# SCH_orion-rf_2026-05-15.net
KiCad netlist of a schematic drawn in EasyEDA
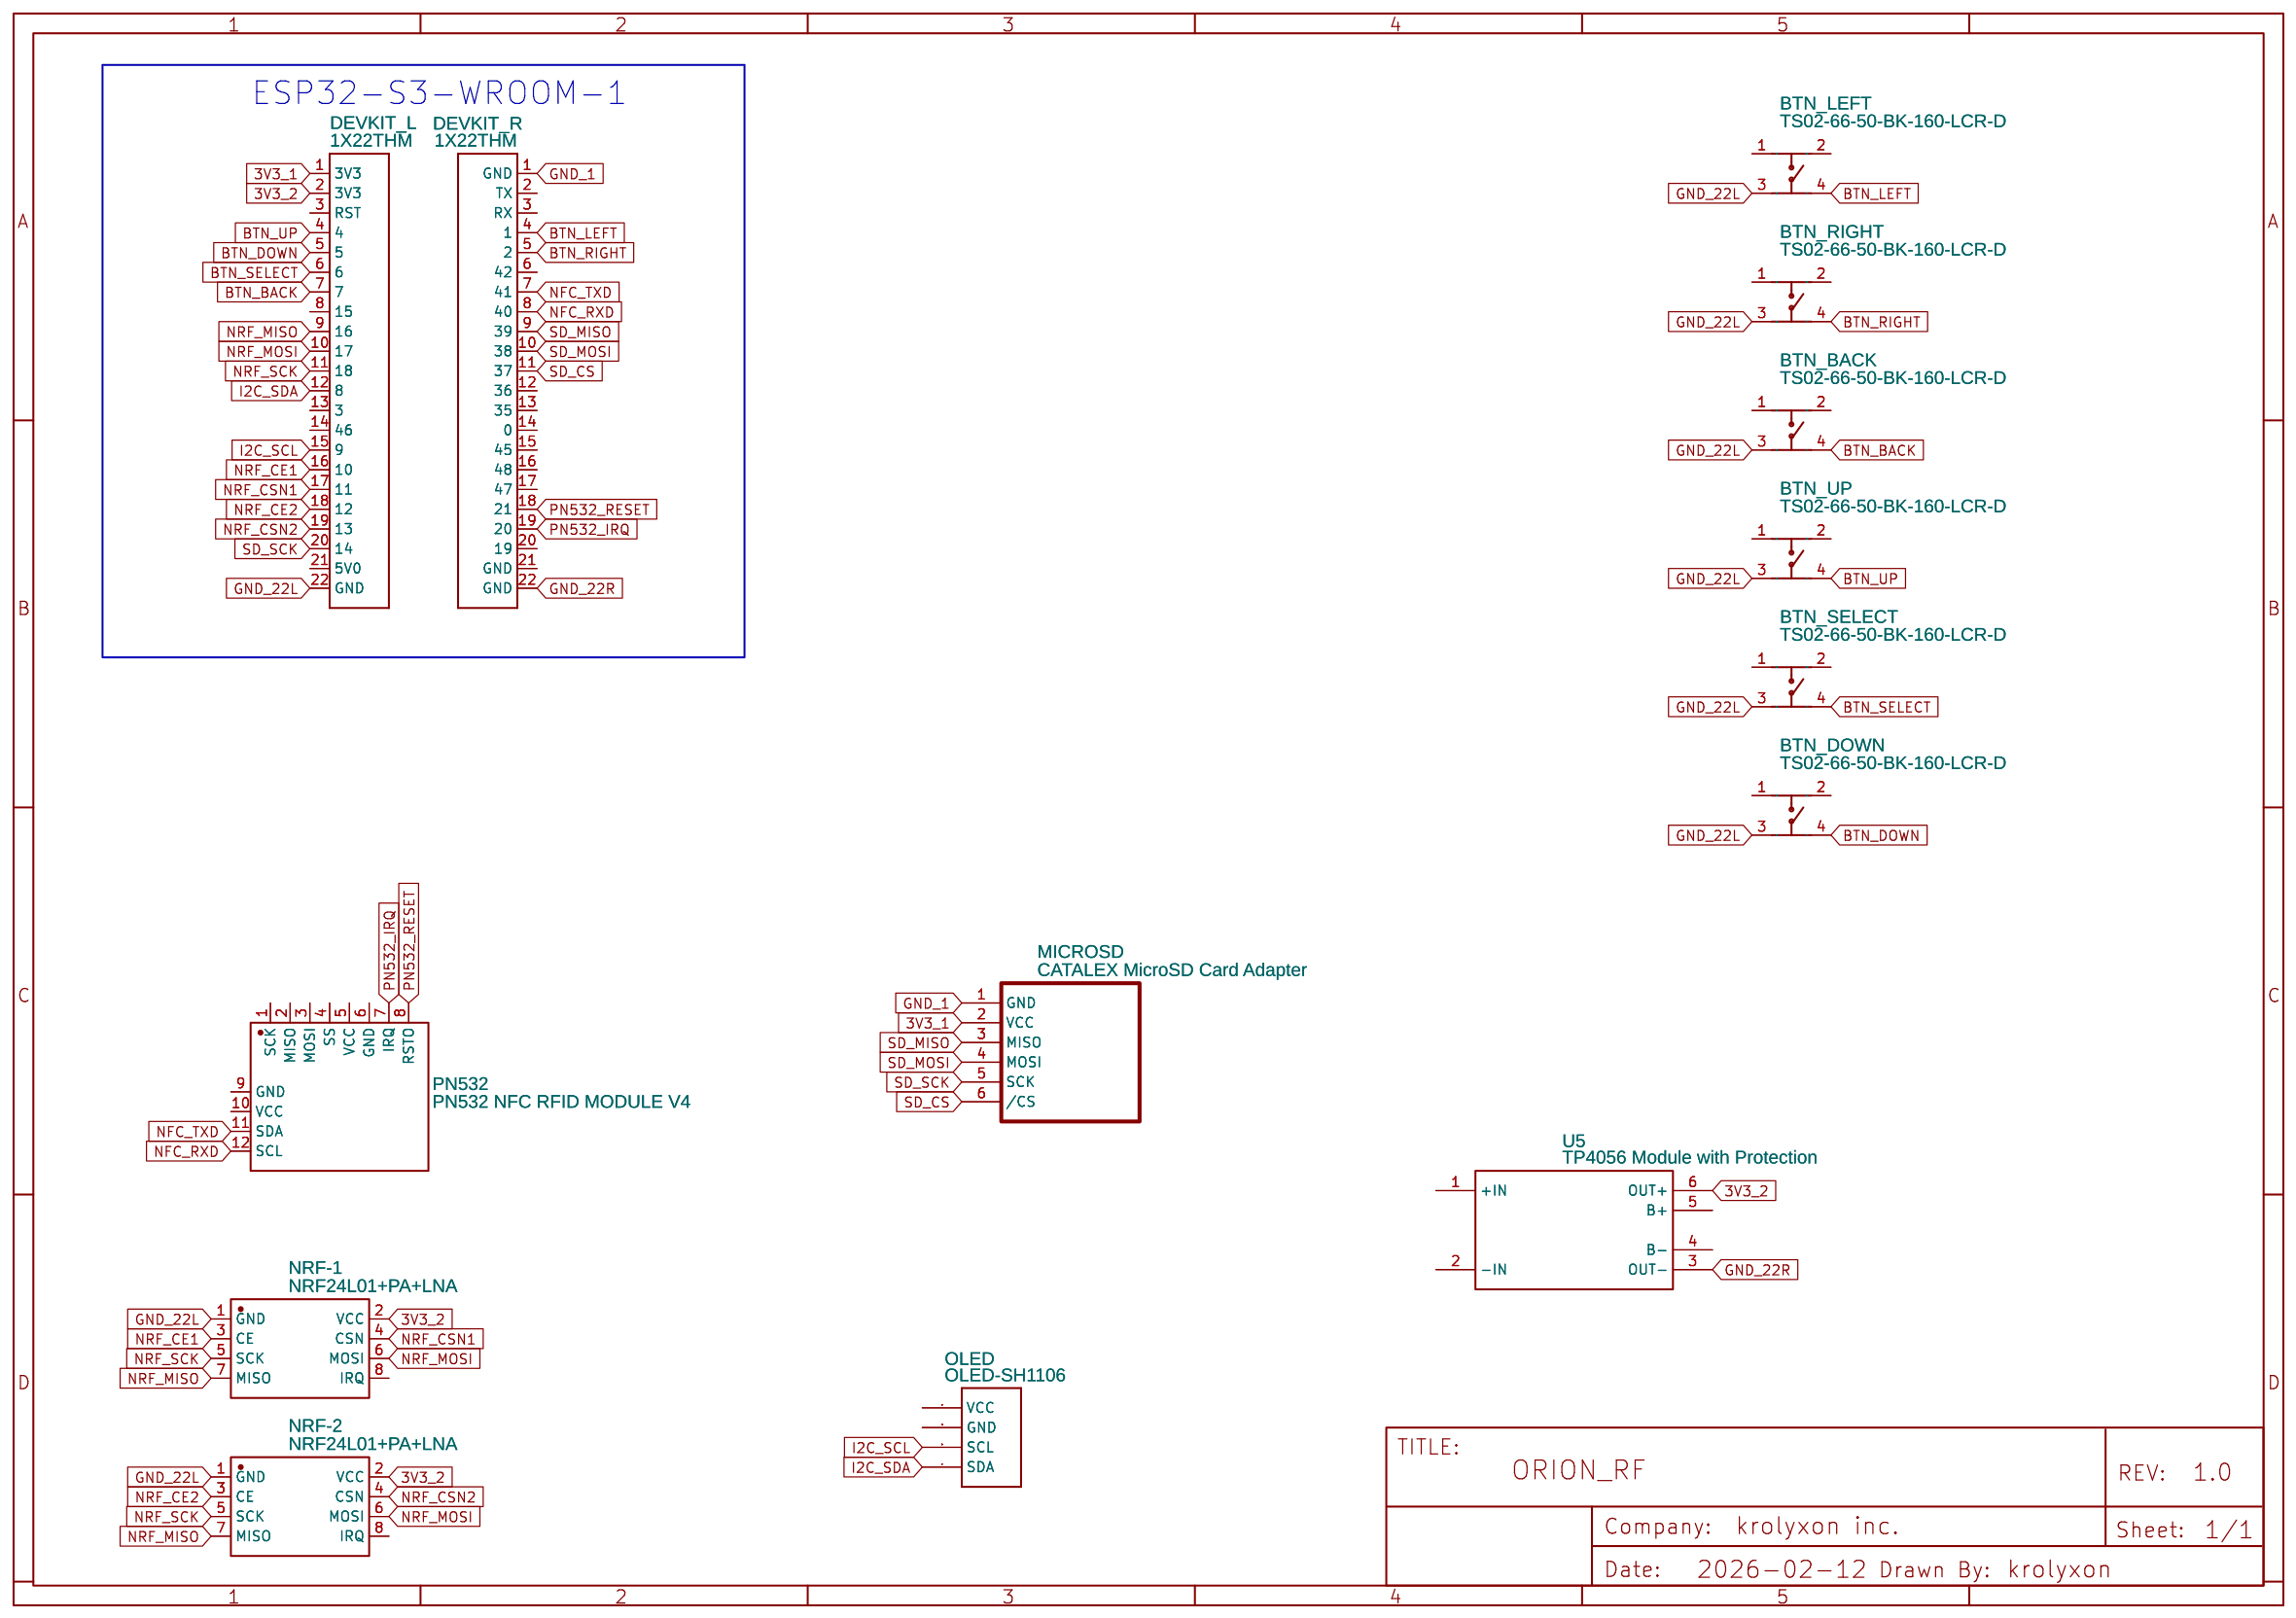
[diagram p0: schematic sheet]

(export (version "E")
  (design (tool "Eeschema 10.0.6"))
  (components
    (comp (ref "BTN_BACK")
      (value "TS02-66-50-BK-160-LCR-D")
      (fields (field (name "Manufacturer") "CUI"))
      (libsource (lib "") (part "TS02-66-50-BK-160-LCR-D"))
    )
    (comp (ref "BTN_DOWN")
      (value "TS02-66-50-BK-160-LCR-D")
      (fields (field (name "Manufacturer") "CUI"))
      (libsource (lib "") (part "TS02-66-50-BK-160-LCR-D_1"))
    )
    (comp (ref "BTN_LEFT")
      (value "TS02-66-50-BK-160-LCR-D")
      (fields (field (name "Manufacturer") "CUI"))
      (libsource (lib "") (part "TS02-66-50-BK-160-LCR-D_3"))
    )
    (comp (ref "BTN_RIGHT")
      (value "TS02-66-50-BK-160-LCR-D")
      (fields (field (name "Manufacturer") "CUI"))
      (libsource (lib "") (part "TS02-66-50-BK-160-LCR-D_5"))
    )
    (comp (ref "BTN_SELECT")
      (value "TS02-66-50-BK-160-LCR-D")
      (fields (field (name "Manufacturer") "CUI"))
      (libsource (lib "") (part "TS02-66-50-BK-160-LCR-D_2"))
    )
    (comp (ref "BTN_UP")
      (value "TS02-66-50-BK-160-LCR-D")
      (fields (field (name "Manufacturer") "CUI"))
      (libsource (lib "") (part "TS02-66-50-BK-160-LCR-D_4"))
    )
    (comp (ref "DEVKIT_L") (value "1X22THM") (libsource (lib "") (part "1X22THM_1")))
    (comp (ref "DEVKIT_R") (value "1X22THM") (libsource (lib "") (part "1X22THM")))
    (comp (ref "MICROSD")
      (value "CATALEX MicroSD Card Adapter")
      (libsource (lib "") (part "CATALEX MicroSD Card Adapter"))
    )
    (comp (ref "NRF-1")
      (value "NRF24L01+PA+LNA")
      (fields (field (name "Manufacturer Part") "nRF24L01+PA+LNA"))
      (libsource (lib "") (part "NRF24L01+PA+LNA"))
    )
    (comp (ref "NRF-2")
      (value "NRF24L01+PA+LNA")
      (fields (field (name "Manufacturer Part") "nRF24L01+PA+LNA"))
      (libsource (lib "") (part "NRF24L01+PA+LNA"))
    )
    (comp (ref "OLED") (value "OLED-SH1106") (libsource (lib "") (part "OLED-SH1106")))
    (comp (ref "PN532")
      (value "PN532 NFC RFID MODULE V4")
      (fields (field (name "Manufacturer Part") "PN532 NFC RFID Module v4"))
      (libsource (lib "") (part "PN532 NFC RFID MODULE V4"))
    )
    (comp (ref "U5")
      (value "TP4056 Module with Protection")
      (libsource (lib "") (part "TP4056 Module with Protection"))
    )
  )
  (nets
    (net (code "1") (name "3V3_1") (class "Default")
      (node (ref "DEVKIT_L") (pin "1") (pinfunction "3V3_1") (pintype "unspecified"))
      (node (ref "MICROSD") (pin "2") (pinfunction "VCC_2") (pintype "unspecified"))
    )
    (net (code "2") (name "3V3_2") (class "Default")
      (node (ref "DEVKIT_L") (pin "2") (pinfunction "3V3_2") (pintype "unspecified"))
      (node (ref "NRF-1") (pin "2") (pinfunction "VCC_2") (pintype "unspecified"))
      (node (ref "NRF-2") (pin "2") (pinfunction "VCC_2") (pintype "unspecified"))
      (node (ref "U5") (pin "6") (pinfunction "OUT+_6") (pintype "unspecified"))
    )
    (net (code "3") (name "BTN_BACK") (class "Default")
      (node (ref "BTN_BACK") (pin "4") (pinfunction "4_4") (pintype "unspecified"))
      (node (ref "DEVKIT_L") (pin "7") (pinfunction "7_7") (pintype "unspecified"))
    )
    (net (code "4") (name "BTN_DOWN") (class "Default")
      (node (ref "BTN_DOWN") (pin "4") (pinfunction "4_4") (pintype "unspecified"))
      (node (ref "DEVKIT_L") (pin "5") (pinfunction "5_5") (pintype "unspecified"))
    )
    (net (code "5") (name "BTN_LEFT") (class "Default")
      (node (ref "BTN_LEFT") (pin "4") (pinfunction "4_4") (pintype "unspecified"))
      (node (ref "DEVKIT_R") (pin "4") (pinfunction "1_4") (pintype "unspecified"))
    )
    (net (code "6") (name "BTN_RIGHT") (class "Default")
      (node (ref "BTN_RIGHT") (pin "4") (pinfunction "4_4") (pintype "unspecified"))
      (node (ref "DEVKIT_R") (pin "5") (pinfunction "2_5") (pintype "unspecified"))
    )
    (net (code "7") (name "BTN_SELECT") (class "Default")
      (node (ref "BTN_SELECT") (pin "4") (pinfunction "4_4") (pintype "unspecified"))
      (node (ref "DEVKIT_L") (pin "6") (pinfunction "6_6") (pintype "unspecified"))
    )
    (net (code "8") (name "BTN_UP") (class "Default")
      (node (ref "BTN_UP") (pin "4") (pinfunction "4_4") (pintype "unspecified"))
      (node (ref "DEVKIT_L") (pin "4") (pinfunction "4_4") (pintype "unspecified"))
    )
    (net (code "9") (name "GND_1") (class "Default")
      (node (ref "DEVKIT_R") (pin "1") (pinfunction "GND_1") (pintype "unspecified"))
      (node (ref "MICROSD") (pin "1") (pinfunction "GND_1") (pintype "unspecified"))
    )
    (net (code "10") (name "GND_22L") (class "Default")
      (node (ref "BTN_BACK") (pin "3") (pinfunction "3_3") (pintype "unspecified"))
      (node (ref "BTN_DOWN") (pin "3") (pinfunction "3_3") (pintype "unspecified"))
      (node (ref "BTN_LEFT") (pin "3") (pinfunction "3_3") (pintype "unspecified"))
      (node (ref "BTN_RIGHT") (pin "3") (pinfunction "3_3") (pintype "unspecified"))
      (node (ref "BTN_SELECT") (pin "3") (pinfunction "3_3") (pintype "unspecified"))
      (node (ref "BTN_UP") (pin "3") (pinfunction "3_3") (pintype "unspecified"))
      (node (ref "DEVKIT_L") (pin "22") (pinfunction "GND_22") (pintype "unspecified"))
      (node (ref "NRF-1") (pin "1") (pinfunction "GND_1") (pintype "unspecified"))
      (node (ref "NRF-2") (pin "1") (pinfunction "GND_1") (pintype "unspecified"))
    )
    (net (code "11") (name "GND_22R") (class "Default")
      (node (ref "DEVKIT_R") (pin "22") (pinfunction "GND_22") (pintype "unspecified"))
      (node (ref "U5") (pin "3") (pinfunction "OUT-_3") (pintype "unspecified"))
    )
    (net (code "12") (name "I2C_SCL") (class "Default")
      (node (ref "DEVKIT_L") (pin "15") (pinfunction "9_15") (pintype "unspecified"))
      (node (ref "OLED") (pin "3") (pinfunction "SCL_3") (pintype "unspecified"))
    )
    (net (code "13") (name "I2C_SDA") (class "Default")
      (node (ref "DEVKIT_L") (pin "12") (pinfunction "8_12") (pintype "unspecified"))
      (node (ref "OLED") (pin "4") (pinfunction "SDA_4") (pintype "unspecified"))
    )
    (net (code "14") (name "NFC_RXD") (class "Default")
      (node (ref "DEVKIT_R") (pin "8") (pinfunction "40_8") (pintype "unspecified"))
      (node (ref "PN532") (pin "12") (pinfunction "SCL_12") (pintype "unspecified"))
    )
    (net (code "15") (name "NFC_TXD") (class "Default")
      (node (ref "DEVKIT_R") (pin "7") (pinfunction "41_7") (pintype "unspecified"))
      (node (ref "PN532") (pin "11") (pinfunction "SDA_11") (pintype "unspecified"))
    )
    (net (code "16") (name "NRF_CE1") (class "Default")
      (node (ref "DEVKIT_L") (pin "16") (pinfunction "10_16") (pintype "unspecified"))
      (node (ref "NRF-1") (pin "3") (pinfunction "CE_3") (pintype "unspecified"))
    )
    (net (code "17") (name "NRF_CE2") (class "Default")
      (node (ref "DEVKIT_L") (pin "18") (pinfunction "12_18") (pintype "unspecified"))
      (node (ref "NRF-2") (pin "3") (pinfunction "CE_3") (pintype "unspecified"))
    )
    (net (code "18") (name "NRF_CSN1") (class "Default")
      (node (ref "DEVKIT_L") (pin "17") (pinfunction "11_17") (pintype "unspecified"))
      (node (ref "NRF-1") (pin "4") (pinfunction "CSN_4") (pintype "unspecified"))
    )
    (net (code "19") (name "NRF_CSN2") (class "Default")
      (node (ref "DEVKIT_L") (pin "19") (pinfunction "13_19") (pintype "unspecified"))
      (node (ref "NRF-2") (pin "4") (pinfunction "CSN_4") (pintype "unspecified"))
    )
    (net (code "20") (name "NRF_MISO") (class "Default")
      (node (ref "DEVKIT_L") (pin "9") (pinfunction "16_9") (pintype "unspecified"))
      (node (ref "NRF-1") (pin "7") (pinfunction "MISO_7") (pintype "unspecified"))
      (node (ref "NRF-2") (pin "7") (pinfunction "MISO_7") (pintype "unspecified"))
    )
    (net (code "21") (name "NRF_MOSI") (class "Default")
      (node (ref "DEVKIT_L") (pin "10") (pinfunction "17_10") (pintype "unspecified"))
      (node (ref "NRF-1") (pin "6") (pinfunction "MOSI_6") (pintype "unspecified"))
      (node (ref "NRF-2") (pin "6") (pinfunction "MOSI_6") (pintype "unspecified"))
    )
    (net (code "22") (name "NRF_SCK") (class "Default")
      (node (ref "DEVKIT_L") (pin "11") (pinfunction "18_11") (pintype "unspecified"))
      (node (ref "NRF-1") (pin "5") (pinfunction "SCK_5") (pintype "unspecified"))
      (node (ref "NRF-2") (pin "5") (pinfunction "SCK_5") (pintype "unspecified"))
    )
    (net (code "23") (name "PN532_IRQ") (class "Default")
      (node (ref "DEVKIT_R") (pin "19") (pinfunction "20_19") (pintype "unspecified"))
      (node (ref "PN532") (pin "7") (pinfunction "IRQ_7") (pintype "unspecified"))
    )
    (net (code "24") (name "PN532_RESET") (class "Default")
      (node (ref "DEVKIT_R") (pin "18") (pinfunction "21_18") (pintype "unspecified"))
      (node (ref "PN532") (pin "8") (pinfunction "RSTO_8") (pintype "unspecified"))
    )
    (net (code "25") (name "SD_CS") (class "Default")
      (node (ref "DEVKIT_R") (pin "11") (pinfunction "37_11") (pintype "unspecified"))
      (node (ref "MICROSD") (pin "6") (pinfunction "/CS_6") (pintype "unspecified"))
    )
    (net (code "26") (name "SD_MISO") (class "Default")
      (node (ref "DEVKIT_R") (pin "9") (pinfunction "39_9") (pintype "unspecified"))
      (node (ref "MICROSD") (pin "3") (pinfunction "MISO_3") (pintype "unspecified"))
    )
    (net (code "27") (name "SD_MOSI") (class "Default")
      (node (ref "DEVKIT_R") (pin "10") (pinfunction "38_10") (pintype "unspecified"))
      (node (ref "MICROSD") (pin "4") (pinfunction "MOSI_4") (pintype "unspecified"))
    )
    (net (code "28") (name "SD_SCK") (class "Default")
      (node (ref "DEVKIT_L") (pin "20") (pinfunction "14_20") (pintype "unspecified"))
      (node (ref "MICROSD") (pin "5") (pinfunction "SCK_5") (pintype "unspecified"))
    )
    (net (code "29") (name "unconnected-(BTN_BACK-Pad1)") (class "Default")
      (node (ref "BTN_BACK") (pin "1") (pinfunction "1_1") (pintype "unspecified"))
    )
    (net (code "30") (name "unconnected-(BTN_BACK-Pad2)") (class "Default")
      (node (ref "BTN_BACK") (pin "2") (pinfunction "2_2") (pintype "unspecified"))
    )
    (net (code "31") (name "unconnected-(BTN_DOWN-Pad1)") (class "Default")
      (node (ref "BTN_DOWN") (pin "1") (pinfunction "1_1") (pintype "unspecified"))
    )
    (net (code "32") (name "unconnected-(BTN_DOWN-Pad2)") (class "Default")
      (node (ref "BTN_DOWN") (pin "2") (pinfunction "2_2") (pintype "unspecified"))
    )
    (net (code "33") (name "unconnected-(BTN_LEFT-Pad1)") (class "Default")
      (node (ref "BTN_LEFT") (pin "1") (pinfunction "1_1") (pintype "unspecified"))
    )
    (net (code "34") (name "unconnected-(BTN_LEFT-Pad2)") (class "Default")
      (node (ref "BTN_LEFT") (pin "2") (pinfunction "2_2") (pintype "unspecified"))
    )
    (net (code "35") (name "unconnected-(BTN_RIGHT-Pad1)") (class "Default")
      (node (ref "BTN_RIGHT") (pin "1") (pinfunction "1_1") (pintype "unspecified"))
    )
    (net (code "36") (name "unconnected-(BTN_RIGHT-Pad2)") (class "Default")
      (node (ref "BTN_RIGHT") (pin "2") (pinfunction "2_2") (pintype "unspecified"))
    )
    (net (code "37") (name "unconnected-(BTN_SELECT-Pad1)") (class "Default")
      (node (ref "BTN_SELECT") (pin "1") (pinfunction "1_1") (pintype "unspecified"))
    )
    (net (code "38") (name "unconnected-(BTN_SELECT-Pad2)") (class "Default")
      (node (ref "BTN_SELECT") (pin "2") (pinfunction "2_2") (pintype "unspecified"))
    )
    (net (code "39") (name "unconnected-(BTN_UP-Pad1)") (class "Default")
      (node (ref "BTN_UP") (pin "1") (pinfunction "1_1") (pintype "unspecified"))
    )
    (net (code "40") (name "unconnected-(BTN_UP-Pad2)") (class "Default")
      (node (ref "BTN_UP") (pin "2") (pinfunction "2_2") (pintype "unspecified"))
    )
    (net (code "41") (name "unconnected-(DEVKIT_L-3-Pad13)") (class "Default")
      (node (ref "DEVKIT_L") (pin "13") (pinfunction "3_13") (pintype "unspecified"))
    )
    (net (code "42") (name "unconnected-(DEVKIT_L-5V0-Pad21)") (class "Default")
      (node (ref "DEVKIT_L") (pin "21") (pinfunction "5V0_21") (pintype "unspecified"))
    )
    (net (code "43") (name "unconnected-(DEVKIT_L-15-Pad8)") (class "Default")
      (node (ref "DEVKIT_L") (pin "8") (pinfunction "15_8") (pintype "unspecified"))
    )
    (net (code "44") (name "unconnected-(DEVKIT_L-46-Pad14)") (class "Default")
      (node (ref "DEVKIT_L") (pin "14") (pinfunction "46_14") (pintype "unspecified"))
    )
    (net (code "45") (name "unconnected-(DEVKIT_L-RST-Pad3)") (class "Default")
      (node (ref "DEVKIT_L") (pin "3") (pinfunction "RST_3") (pintype "unspecified"))
    )
    (net (code "46") (name "unconnected-(DEVKIT_R-0-Pad14)") (class "Default")
      (node (ref "DEVKIT_R") (pin "14") (pinfunction "0_14") (pintype "unspecified"))
    )
    (net (code "47") (name "unconnected-(DEVKIT_R-19-Pad20)") (class "Default")
      (node (ref "DEVKIT_R") (pin "20") (pinfunction "19_20") (pintype "unspecified"))
    )
    (net (code "48") (name "unconnected-(DEVKIT_R-35-Pad13)") (class "Default")
      (node (ref "DEVKIT_R") (pin "13") (pinfunction "35_13") (pintype "unspecified"))
    )
    (net (code "49") (name "unconnected-(DEVKIT_R-36-Pad12)") (class "Default")
      (node (ref "DEVKIT_R") (pin "12") (pinfunction "36_12") (pintype "unspecified"))
    )
    (net (code "50") (name "unconnected-(DEVKIT_R-42-Pad6)") (class "Default")
      (node (ref "DEVKIT_R") (pin "6") (pinfunction "42_6") (pintype "unspecified"))
    )
    (net (code "51") (name "unconnected-(DEVKIT_R-45-Pad15)") (class "Default")
      (node (ref "DEVKIT_R") (pin "15") (pinfunction "45_15") (pintype "unspecified"))
    )
    (net (code "52") (name "unconnected-(DEVKIT_R-47-Pad17)") (class "Default")
      (node (ref "DEVKIT_R") (pin "17") (pinfunction "47_17") (pintype "unspecified"))
    )
    (net (code "53") (name "unconnected-(DEVKIT_R-48-Pad16)") (class "Default")
      (node (ref "DEVKIT_R") (pin "16") (pinfunction "48_16") (pintype "unspecified"))
    )
    (net (code "54") (name "unconnected-(DEVKIT_R-GND-Pad21)") (class "Default")
      (node (ref "DEVKIT_R") (pin "21") (pinfunction "GND_21") (pintype "unspecified"))
    )
    (net (code "55") (name "unconnected-(DEVKIT_R-RX-Pad3)") (class "Default")
      (node (ref "DEVKIT_R") (pin "3") (pinfunction "RX_3") (pintype "unspecified"))
    )
    (net (code "56") (name "unconnected-(DEVKIT_R-TX-Pad2)") (class "Default")
      (node (ref "DEVKIT_R") (pin "2") (pinfunction "TX_2") (pintype "unspecified"))
    )
    (net (code "57") (name "unconnected-(NRF-1-IRQ-Pad8)") (class "Default")
      (node (ref "NRF-1") (pin "8") (pinfunction "IRQ_8") (pintype "unspecified"))
    )
    (net (code "58") (name "unconnected-(NRF-2-IRQ-Pad8)") (class "Default")
      (node (ref "NRF-2") (pin "8") (pinfunction "IRQ_8") (pintype "unspecified"))
    )
    (net (code "59") (name "unconnected-(OLED-GND-Pad2)") (class "Default")
      (node (ref "OLED") (pin "2") (pinfunction "GND_2") (pintype "unspecified"))
    )
    (net (code "60") (name "unconnected-(OLED-VCC-Pad1)") (class "Default")
      (node (ref "OLED") (pin "1") (pinfunction "VCC_1") (pintype "unspecified"))
    )
    (net (code "61") (name "unconnected-(PN532-GND-Pad6)") (class "Default")
      (node (ref "PN532") (pin "6") (pinfunction "GND_6") (pintype "unspecified"))
    )
    (net (code "62") (name "unconnected-(PN532-GND-Pad9)") (class "Default")
      (node (ref "PN532") (pin "9") (pinfunction "GND_9") (pintype "unspecified"))
    )
    (net (code "63") (name "unconnected-(PN532-MISO-Pad2)") (class "Default")
      (node (ref "PN532") (pin "2") (pinfunction "MISO_2") (pintype "unspecified"))
    )
    (net (code "64") (name "unconnected-(PN532-MOSI-Pad3)") (class "Default")
      (node (ref "PN532") (pin "3") (pinfunction "MOSI_3") (pintype "unspecified"))
    )
    (net (code "65") (name "unconnected-(PN532-SCK-Pad1)") (class "Default")
      (node (ref "PN532") (pin "1") (pinfunction "SCK_1") (pintype "unspecified"))
    )
    (net (code "66") (name "unconnected-(PN532-SS-Pad4)") (class "Default")
      (node (ref "PN532") (pin "4") (pinfunction "SS_4") (pintype "unspecified"))
    )
    (net (code "67") (name "unconnected-(PN532-VCC-Pad5)") (class "Default")
      (node (ref "PN532") (pin "5") (pinfunction "VCC_5") (pintype "unspecified"))
    )
    (net (code "68") (name "unconnected-(PN532-VCC-Pad10)") (class "Default")
      (node (ref "PN532") (pin "10") (pinfunction "VCC_10") (pintype "unspecified"))
    )
    (net (code "69") (name "unconnected-(U5-+IN-Pad1)") (class "Default")
      (node (ref "U5") (pin "1") (pinfunction "+IN_1") (pintype "unspecified"))
    )
    (net (code "70") (name "unconnected-(U5--IN-Pad2)") (class "Default")
      (node (ref "U5") (pin "2") (pinfunction "-IN_2") (pintype "unspecified"))
    )
    (net (code "71") (name "unconnected-(U5-B+-Pad5)") (class "Default")
      (node (ref "U5") (pin "5") (pinfunction "B+_5") (pintype "unspecified"))
    )
    (net (code "72") (name "unconnected-(U5-B--Pad4)") (class "Default")
      (node (ref "U5") (pin "4") (pinfunction "B-_4") (pintype "unspecified"))
    )
  )
)
